# Sheet1.net
KiCad netlist of a schematic drawn in Altium Designer
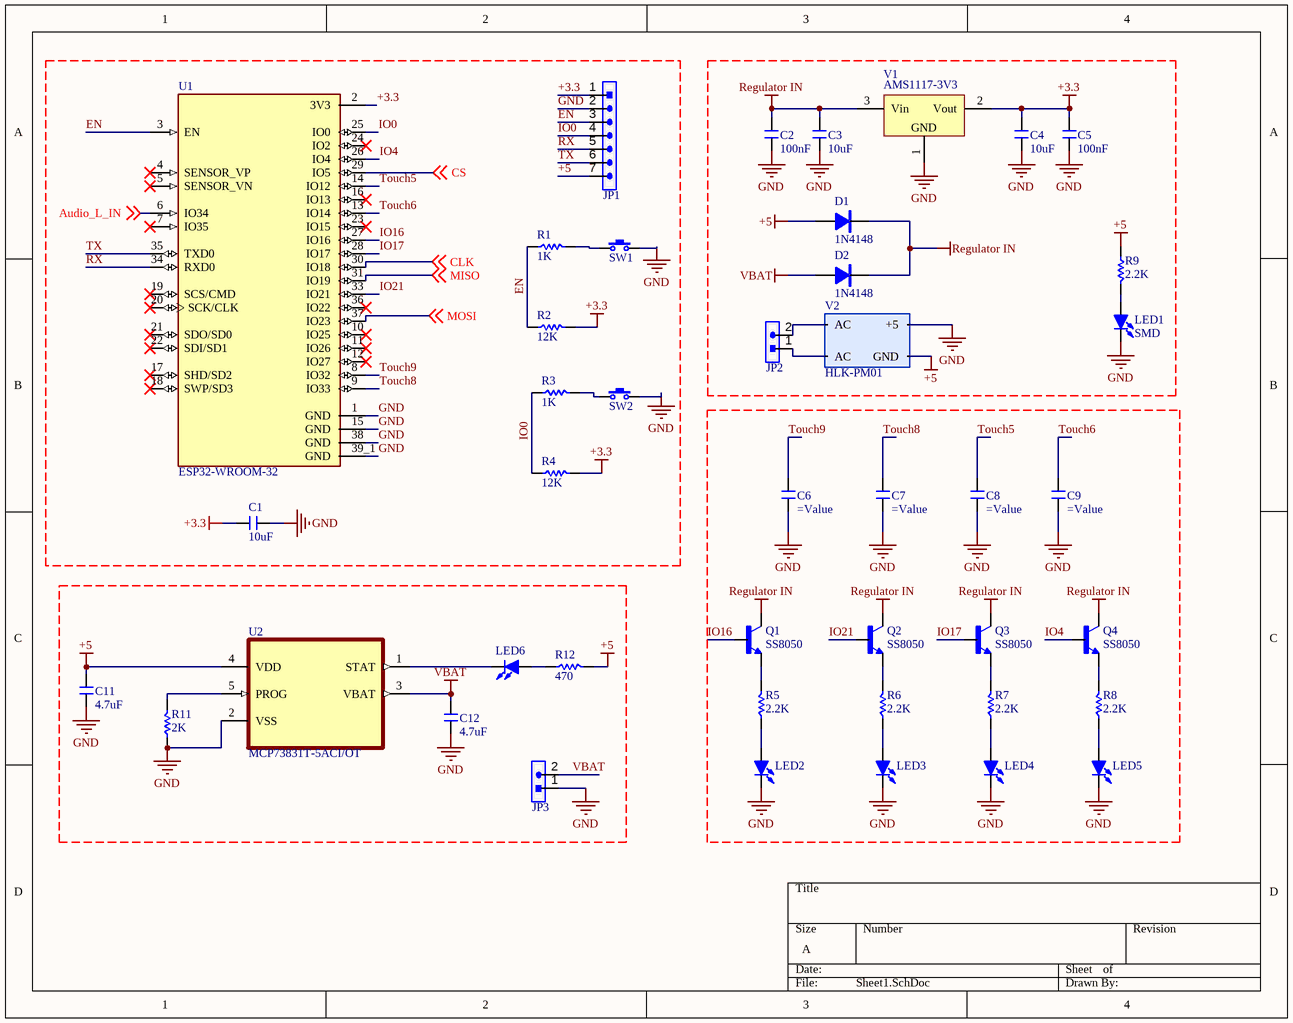
[diagram p0: Sheet1.SchDoc]

(export (version "E")
  (design (tool "Eeschema 10.0.6"))
  (components
    (comp (ref "C1")
      (value "10uF")
      (footprint "C 0805")
      (description "Non-polar patch capacitor")
      (fields (field (name "版权归属") "源创客"))
      (libsource (lib "Passive (Resistor-Capacitor-Inductor-Veristor-Ferrite)") (part "C"))
    )
    (comp (ref "C2")
      (value "100nF")
      (footprint "C 0805")
      (description "Non-polar patch capacitor")
      (fields (field (name "版权归属") "源创客"))
      (libsource (lib "Passive (Resistor-Capacitor-Inductor-Veristor-Ferrite)") (part "C"))
    )
    (comp (ref "C3")
      (value "10uF")
      (footprint "C 0805")
      (description "Non-polar patch capacitor")
      (fields (field (name "版权归属") "源创客"))
      (libsource (lib "Passive (Resistor-Capacitor-Inductor-Veristor-Ferrite)") (part "C"))
    )
    (comp (ref "C4")
      (value "10uF")
      (footprint "C 0805")
      (description "Non-polar patch capacitor")
      (fields (field (name "版权归属") "源创客"))
      (libsource (lib "Passive (Resistor-Capacitor-Inductor-Veristor-Ferrite)") (part "C"))
    )
    (comp (ref "C5")
      (value "100nF")
      (footprint "C 0805")
      (description "Non-polar patch capacitor")
      (fields (field (name "版权归属") "源创客"))
      (libsource (lib "Passive (Resistor-Capacitor-Inductor-Veristor-Ferrite)") (part "C"))
    )
    (comp (ref "C6")
      (value "~")
      (footprint "C 0805")
      (description "Non-polar patch capacitor")
      (fields (field (name "版权归属") "源创客"))
      (libsource (lib "Passive (Resistor-Capacitor-Inductor-Veristor-Ferrite)") (part "C"))
    )
    (comp (ref "C7")
      (value "~")
      (footprint "C 0805")
      (description "Non-polar patch capacitor")
      (fields (field (name "版权归属") "源创客"))
      (libsource (lib "Passive (Resistor-Capacitor-Inductor-Veristor-Ferrite)") (part "C"))
    )
    (comp (ref "C8")
      (value "~")
      (footprint "C 0805")
      (description "Non-polar patch capacitor")
      (fields (field (name "版权归属") "源创客"))
      (libsource (lib "Passive (Resistor-Capacitor-Inductor-Veristor-Ferrite)") (part "C"))
    )
    (comp (ref "C9")
      (value "~")
      (footprint "C 0805")
      (description "Non-polar patch capacitor")
      (fields (field (name "版权归属") "源创客"))
      (libsource (lib "Passive (Resistor-Capacitor-Inductor-Veristor-Ferrite)") (part "C"))
    )
    (comp (ref "C11")
      (value "4.7uF")
      (footprint "C 0805")
      (description "Non-polar patch capacitor")
      (fields (field (name "版权归属") "源创客"))
      (libsource (lib "Passive (Resistor-Capacitor-Inductor-Veristor-Ferrite)") (part "C"))
    )
    (comp (ref "C12")
      (value "4.7uF")
      (footprint "C 0805")
      (description "Non-polar patch capacitor")
      (fields (field (name "版权归属") "源创客"))
      (libsource (lib "Passive (Resistor-Capacitor-Inductor-Veristor-Ferrite)") (part "C"))
    )
    (comp (ref "D1")
      (value "1N4148")
      (footprint "MINI_MELF (LL34)")
      (description "High speed switching diode")
      (fields (field (name "版权归属") "源创客"))
      (libsource (lib "Diode-Zener-Rectifier Bridge") (part "1N4148"))
    )
    (comp (ref "D2")
      (value "1N4148")
      (footprint "MINI_MELF (LL34)")
      (description "High speed switching diode")
      (fields (field (name "版权归属") "源创客"))
      (libsource (lib "Diode-Zener-Rectifier Bridge") (part "1N4148"))
    )
    (comp (ref "JP1")
      (value "HDR-1X7")
      (footprint "HDR-1X7")
      (description "7P Connector")
      (fields (field (name "版权归属") "源创客"))
      (libsource (lib "Connectors") (part "Header 7"))
    )
    (comp (ref "JP2")
      (value "HDR-1X2")
      (footprint "KF2EDGK-2P")
      (description "2P Connector")
      (fields (field (name "版权归属") "源创客"))
      (libsource (lib "Connectors") (part "Header 2"))
    )
    (comp (ref "JP3")
      (value "HDR-1X2")
      (footprint "HDR-1X2")
      (description "2P Connector")
      (fields (field (name "版权归属") "源创客"))
      (libsource (lib "Connectors") (part "Header 2"))
    )
    (comp (ref "LED1")
      (value "SMD")
      (footprint "LED 0805R")
      (description "RED LED")
      (fields (field (name "版权归属") "源创客"))
      (libsource (lib "LED") (part "LED-SMD"))
    )
    (comp (ref "LED2")
      (value "~")
      (footprint "LED 5MM-B")
      (description "5mm plug-in LED")
      (fields (field (name "版权归属") "源创客"))
      (libsource (lib "LED") (part "LED-5MM"))
    )
    (comp (ref "LED3")
      (value "~")
      (footprint "LED 5MM-B")
      (description "5mm plug-in LED")
      (fields (field (name "版权归属") "源创客"))
      (libsource (lib "LED") (part "LED-5MM"))
    )
    (comp (ref "LED4")
      (value "~")
      (footprint "LED 5MM-B")
      (description "5mm plug-in LED")
      (fields (field (name "版权归属") "源创客"))
      (libsource (lib "LED") (part "LED-5MM"))
    )
    (comp (ref "LED5")
      (value "~")
      (footprint "LED 5MM-B")
      (description "5mm plug-in LED")
      (fields (field (name "版权归属") "源创客"))
      (libsource (lib "LED") (part "LED-5MM"))
    )
    (comp (ref "LED6")
      (value "LED-SMD")
      (footprint "LED 0805G")
      (description "Patch LED")
      (fields (field (name "版权归属") "源创客"))
      (libsource (lib "LED") (part "LED-SMD"))
    )
    (comp (ref "Q1")
      (value "SS8050")
      (footprint "SOT23-BEC")
      (description "Bipolar _BJT_ Transistor NPN General Purpose Amplifier Surface Mount")
      (fields (field (name "MF") "ON Semiconductor") (field (name "MP") "BCW31"))
      (libsource (lib "BCW31_") (part "BCW31*"))
    )
    (comp (ref "Q2")
      (value "SS8050")
      (footprint "SOT23-BEC")
      (description "Bipolar _BJT_ Transistor NPN General Purpose Amplifier Surface Mount")
      (fields (field (name "MF") "ON Semiconductor") (field (name "MP") "BCW31"))
      (libsource (lib "BCW31_") (part "BCW31*"))
    )
    (comp (ref "Q3")
      (value "SS8050")
      (footprint "SOT23-BEC")
      (description "Bipolar _BJT_ Transistor NPN General Purpose Amplifier Surface Mount")
      (fields (field (name "MF") "ON Semiconductor") (field (name "MP") "BCW31"))
      (libsource (lib "BCW31_") (part "BCW31*"))
    )
    (comp (ref "Q4")
      (value "SS8050")
      (footprint "SOT23-BEC")
      (description "Bipolar _BJT_ Transistor NPN General Purpose Amplifier Surface Mount")
      (fields (field (name "MF") "ON Semiconductor") (field (name "MP") "BCW31"))
      (libsource (lib "BCW31_") (part "BCW31*"))
    )
    (comp (ref "R1")
      (value "1K")
      (footprint "R 0805")
      (description "Chip resistor")
      (fields (field (name "版权归属") "源创客"))
      (libsource (lib "AltiumDesigner PCB Library") (part "R"))
    )
    (comp (ref "R2")
      (value "12K")
      (footprint "R 0805")
      (description "Chip resistor")
      (fields (field (name "版权归属") "源创客"))
      (libsource (lib "AltiumDesigner PCB Library") (part "R"))
    )
    (comp (ref "R3")
      (value "1K")
      (footprint "R 0805")
      (description "Chip resistor")
      (fields (field (name "版权归属") "源创客"))
      (libsource (lib "AltiumDesigner PCB Library") (part "R"))
    )
    (comp (ref "R4")
      (value "12K")
      (footprint "R 0805")
      (description "Chip resistor")
      (fields (field (name "版权归属") "源创客"))
      (libsource (lib "AltiumDesigner PCB Library") (part "R"))
    )
    (comp (ref "R5")
      (value "2.2K")
      (footprint "R 0805")
      (description "Chip resistor")
      (fields (field (name "版权归属") "源创客"))
      (libsource (lib "AltiumDesigner PCB Library") (part "R"))
    )
    (comp (ref "R6")
      (value "2.2K")
      (footprint "R 0805")
      (description "Chip resistor")
      (fields (field (name "版权归属") "源创客"))
      (libsource (lib "AltiumDesigner PCB Library") (part "R"))
    )
    (comp (ref "R7")
      (value "2.2K")
      (footprint "R 0805")
      (description "Chip resistor")
      (fields (field (name "版权归属") "源创客"))
      (libsource (lib "AltiumDesigner PCB Library") (part "R"))
    )
    (comp (ref "R8")
      (value "2.2K")
      (footprint "R 0805")
      (description "Chip resistor")
      (fields (field (name "版权归属") "源创客"))
      (libsource (lib "AltiumDesigner PCB Library") (part "R"))
    )
    (comp (ref "R9")
      (value "2.2K")
      (footprint "R 0805")
      (description "Chip resistor")
      (fields (field (name "版权归属") "源创客"))
      (libsource (lib "Passive (Resistor-Capacitor-Inductor-Veristor-Ferrite)") (part "R"))
    )
    (comp (ref "R11")
      (value "2K")
      (footprint "R 0805")
      (description "Chip resistor")
      (fields (field (name "版权归属") "源创客"))
      (libsource (lib "Passive (Resistor-Capacitor-Inductor-Veristor-Ferrite)") (part "R"))
    )
    (comp (ref "R12")
      (value "470")
      (footprint "R 0805")
      (description "Chip resistor")
      (fields (field (name "版权归属") "源创客"))
      (libsource (lib "Passive (Resistor-Capacitor-Inductor-Veristor-Ferrite)") (part "R"))
    )
    (comp (ref "SW1")
      (value "3x6x5")
      (footprint "TSW SMD-3*6*2.5")
      (description "3x6 tact switch")
      (fields (field (name "版权归属") "源创客"))
      (libsource (lib "Button") (part "TSW 3x6"))
    )
    (comp (ref "SW2")
      (value "3x6x5")
      (footprint "TSW SMD-3*6*2.5")
      (description "3x6 tact switch")
      (fields (field (name "版权归属") "源创客"))
      (libsource (lib "Button") (part "TSW 3x6"))
    )
    (comp (ref "U1")
      (value "ESP32-WROOM-32")
      (footprint "MODULE_ESP32-WROOM-32")
      (description "Bluetooth, WiFi Transceiver Module 2.4GHz ~ 2.5GHz Surface Mount")
      (fields (field (name "MF") "Espressif Systems") (field (name "DIGI-KEY_PART_NUMBER") "1904-1010-1-ND"))
      (libsource (lib "ESP32-WROOM-32") (part "ESP32-WROOM-32"))
    )
    (comp (ref "U2")
      (value "MCP73831T-5ACI/OT")
      (footprint "SOT95P280X145-5N")
      (description "Charger IC Lithium Ion/Polymer SOT-23-5")
      (fields (field (name "MF") "Microchip"))
      (libsource (lib "MCP73831T-5ACI_OT") (part "MCP73831T-5ACI/OT"))
    )
    (comp (ref "V1")
      (value "AMS1117-3V3")
      (footprint "SOT223_L")
      (description "Three-terminal regulator chip")
      (fields (field (name "版权归属") "源创客"))
      (libsource (lib "Integrated Circuit") (part "AMS1117"))
    )
    (comp (ref "V2")
      (value "HLK-PM01")
      (footprint "HLKPM01")
      (fields (field (name "MF") "Hi-link") (field (name "MP") "hlk-pm01"))
      (libsource (lib "HLK-PM01") (part "HLK-PM01"))
    )
  )
  (nets
    (net (code "1") (name "+3.3") (class "Default")
      (node (ref "C1") (pin "2") (pinfunction "2_2") (pintype "passive"))
      (node (ref "C4") (pin "2") (pinfunction "2_2") (pintype "passive"))
      (node (ref "C5") (pin "2") (pinfunction "2_2") (pintype "passive"))
      (node (ref "JP1") (pin "1") (pintype "passive"))
      (node (ref "R2") (pin "2") (pinfunction "2_2") (pintype "passive"))
      (node (ref "R4") (pin "2") (pinfunction "2_2") (pintype "passive"))
      (node (ref "U1") (pin "2") (pinfunction "3V3_2") (pintype "power_in"))
      (node (ref "V1") (pin "2") (pinfunction "Vout_2") (pintype "passive"))
    )
    (net (code "2") (name "+5") (class "Default")
      (node (ref "C11") (pin "2") (pinfunction "2_2") (pintype "passive"))
      (node (ref "D1") (pin "1") (pinfunction "A_1") (pintype "passive"))
      (node (ref "JP1") (pin "7") (pintype "passive"))
      (node (ref "R12") (pin "2") (pinfunction "2_2") (pintype "passive"))
      (node (ref "R9") (pin "1") (pinfunction "1_1") (pintype "passive"))
      (node (ref "U2") (pin "4") (pinfunction "VDD_4") (pintype "power_in"))
      (node (ref "V2") (pin "4") (pinfunction "GND_4") (pintype "output"))
    )
    (net (code "3") (name "/EN") (class "Default")
      (node (ref "JP1") (pin "3") (pintype "passive"))
      (node (ref "R1") (pin "1") (pinfunction "1_1") (pintype "passive"))
      (node (ref "R2") (pin "1") (pinfunction "1_1") (pintype "passive"))
      (node (ref "U1") (pin "3") (pinfunction "EN_3") (pintype "input"))
    )
    (net (code "4") (name "/IO0") (class "Default")
      (node (ref "JP1") (pin "4") (pintype "passive"))
      (node (ref "R3") (pin "1") (pinfunction "1_1") (pintype "passive"))
      (node (ref "R4") (pin "1") (pinfunction "1_1") (pintype "passive"))
      (node (ref "U1") (pin "25") (pinfunction "IO0_25") (pintype "bidirectional"))
    )
    (net (code "5") (name "/IO4") (class "Default")
      (node (ref "Q4") (pin "B") (pinfunction "B_B") (pintype "passive"))
      (node (ref "U1") (pin "26") (pinfunction "IO4_26") (pintype "bidirectional"))
    )
    (net (code "6") (name "/IO16") (class "Default")
      (node (ref "Q1") (pin "B") (pinfunction "B_B") (pintype "passive"))
      (node (ref "U1") (pin "27") (pinfunction "IO16_27") (pintype "bidirectional"))
    )
    (net (code "7") (name "/IO17") (class "Default")
      (node (ref "Q3") (pin "B") (pinfunction "B_B") (pintype "passive"))
      (node (ref "U1") (pin "28") (pinfunction "IO17_28") (pintype "bidirectional"))
    )
    (net (code "8") (name "/IO21") (class "Default")
      (node (ref "Q2") (pin "B") (pinfunction "B_B") (pintype "passive"))
      (node (ref "U1") (pin "33") (pinfunction "IO21_33") (pintype "bidirectional"))
    )
    (net (code "9") (name "/RX") (class "Default")
      (node (ref "JP1") (pin "5") (pintype "passive"))
      (node (ref "U1") (pin "34") (pinfunction "RXD0_34") (pintype "bidirectional"))
    )
    (net (code "10") (name "/TX") (class "Default")
      (node (ref "JP1") (pin "6") (pintype "passive"))
      (node (ref "U1") (pin "35") (pinfunction "TXD0_35") (pintype "bidirectional"))
    )
    (net (code "11") (name "/Touch5") (class "Default")
      (node (ref "C8") (pin "2") (pinfunction "2_2") (pintype "passive"))
      (node (ref "U1") (pin "14") (pinfunction "IO12_14") (pintype "bidirectional"))
    )
    (net (code "12") (name "/Touch6") (class "Default")
      (node (ref "C9") (pin "2") (pinfunction "2_2") (pintype "passive"))
      (node (ref "U1") (pin "13") (pinfunction "IO14_13") (pintype "bidirectional"))
    )
    (net (code "13") (name "/Touch8") (class "Default")
      (node (ref "C7") (pin "2") (pinfunction "2_2") (pintype "passive"))
      (node (ref "U1") (pin "9") (pinfunction "IO33_9") (pintype "bidirectional"))
    )
    (net (code "14") (name "/Touch9") (class "Default")
      (node (ref "C6") (pin "2") (pinfunction "2_2") (pintype "passive"))
      (node (ref "U1") (pin "8") (pinfunction "IO32_8") (pintype "bidirectional"))
    )
    (net (code "15") (name "Audio_L_IN") (class "Default")
      (node (ref "U1") (pin "6") (pinfunction "IO34_6") (pintype "input"))
    )
    (net (code "16") (name "CLK") (class "Default")
      (node (ref "U1") (pin "30") (pinfunction "IO18_30") (pintype "bidirectional"))
    )
    (net (code "17") (name "CS") (class "Default")
      (node (ref "U1") (pin "29") (pinfunction "IO5_29") (pintype "bidirectional"))
    )
    (net (code "18") (name "GND") (class "Default")
      (node (ref "C1") (pin "1") (pinfunction "1_1") (pintype "passive"))
      (node (ref "C11") (pin "1") (pinfunction "1_1") (pintype "passive"))
      (node (ref "C12") (pin "1") (pinfunction "1_1") (pintype "passive"))
      (node (ref "C2") (pin "1") (pinfunction "1_1") (pintype "passive"))
      (node (ref "C3") (pin "1") (pinfunction "1_1") (pintype "passive"))
      (node (ref "C4") (pin "1") (pinfunction "1_1") (pintype "passive"))
      (node (ref "C5") (pin "1") (pinfunction "1_1") (pintype "passive"))
      (node (ref "C6") (pin "1") (pinfunction "1_1") (pintype "passive"))
      (node (ref "C7") (pin "1") (pinfunction "1_1") (pintype "passive"))
      (node (ref "C8") (pin "1") (pinfunction "1_1") (pintype "passive"))
      (node (ref "C9") (pin "1") (pinfunction "1_1") (pintype "passive"))
      (node (ref "JP1") (pin "2") (pintype "passive"))
      (node (ref "JP3") (pin "1") (pintype "passive"))
      (node (ref "LED1") (pin "2") (pinfunction "K_2") (pintype "passive"))
      (node (ref "LED2") (pin "2") (pinfunction "K_2") (pintype "passive"))
      (node (ref "LED3") (pin "2") (pinfunction "K_2") (pintype "passive"))
      (node (ref "LED4") (pin "2") (pinfunction "K_2") (pintype "passive"))
      (node (ref "LED5") (pin "2") (pinfunction "K_2") (pintype "passive"))
      (node (ref "R11") (pin "1") (pinfunction "1_1") (pintype "passive"))
      (node (ref "SW1") (pin "2") (pinfunction "2_2") (pintype "passive"))
      (node (ref "SW2") (pin "2") (pinfunction "2_2") (pintype "passive"))
      (node (ref "U1") (pin "1") (pinfunction "GND_1") (pintype "power_in"))
      (node (ref "U1") (pin "15") (pinfunction "GND_15") (pintype "power_in"))
      (node (ref "U1") (pin "38") (pinfunction "GND_38") (pintype "power_in"))
      (node (ref "U1") (pin "39_1") (pinfunction "GND_39_1") (pintype "power_in"))
      (node (ref "U2") (pin "2") (pinfunction "VSS_2") (pintype "power_in"))
      (node (ref "V1") (pin "1") (pinfunction "GND_1") (pintype "passive"))
      (node (ref "V2") (pin "3") (pinfunction "+5_3") (pintype "output"))
    )
    (net (code "19") (name "MISO") (class "Default")
      (node (ref "U1") (pin "31") (pinfunction "IO19_31") (pintype "bidirectional"))
    )
    (net (code "20") (name "MOSI") (class "Default")
      (node (ref "U1") (pin "37") (pinfunction "IO23_37") (pintype "bidirectional"))
    )
    (net (code "21") (name "Net-(JP2-Pad1)") (class "Default")
      (node (ref "JP2") (pin "1") (pintype "passive"))
      (node (ref "V2") (pin "2") (pinfunction "AC_2") (pintype "input"))
    )
    (net (code "22") (name "Net-(JP2-Pad2)") (class "Default")
      (node (ref "JP2") (pin "2") (pintype "passive"))
      (node (ref "V2") (pin "1") (pinfunction "AC_1") (pintype "input"))
    )
    (net (code "23") (name "Net-(LED1-A)") (class "Default")
      (node (ref "LED1") (pin "1") (pinfunction "A_1") (pintype "passive"))
      (node (ref "R9") (pin "2") (pinfunction "2_2") (pintype "passive"))
    )
    (net (code "24") (name "Net-(LED2-A)") (class "Default")
      (node (ref "LED2") (pin "1") (pinfunction "A_1") (pintype "passive"))
      (node (ref "R5") (pin "1") (pinfunction "1_1") (pintype "passive"))
    )
    (net (code "25") (name "Net-(LED3-A)") (class "Default")
      (node (ref "LED3") (pin "1") (pinfunction "A_1") (pintype "passive"))
      (node (ref "R6") (pin "1") (pinfunction "1_1") (pintype "passive"))
    )
    (net (code "26") (name "Net-(LED4-A)") (class "Default")
      (node (ref "LED4") (pin "1") (pinfunction "A_1") (pintype "passive"))
      (node (ref "R7") (pin "1") (pinfunction "1_1") (pintype "passive"))
    )
    (net (code "27") (name "Net-(LED5-A)") (class "Default")
      (node (ref "LED5") (pin "1") (pinfunction "A_1") (pintype "passive"))
      (node (ref "R8") (pin "1") (pinfunction "1_1") (pintype "passive"))
    )
    (net (code "28") (name "Net-(LED6-A)") (class "Default")
      (node (ref "LED6") (pin "1") (pinfunction "A_1") (pintype "passive"))
      (node (ref "R12") (pin "1") (pinfunction "1_1") (pintype "passive"))
    )
    (net (code "29") (name "Net-(LED6-K)") (class "Default")
      (node (ref "LED6") (pin "2") (pinfunction "K_2") (pintype "passive"))
      (node (ref "U2") (pin "1") (pinfunction "STAT_1") (pintype "output"))
    )
    (net (code "30") (name "Net-(Q1-PadE)") (class "Default")
      (node (ref "Q1") (pin "E") (pinfunction "E_E") (pintype "passive"))
      (node (ref "R5") (pin "2") (pinfunction "2_2") (pintype "passive"))
    )
    (net (code "31") (name "Net-(Q2-PadE)") (class "Default")
      (node (ref "Q2") (pin "E") (pinfunction "E_E") (pintype "passive"))
      (node (ref "R6") (pin "2") (pinfunction "2_2") (pintype "passive"))
    )
    (net (code "32") (name "Net-(Q3-PadE)") (class "Default")
      (node (ref "Q3") (pin "E") (pinfunction "E_E") (pintype "passive"))
      (node (ref "R7") (pin "2") (pinfunction "2_2") (pintype "passive"))
    )
    (net (code "33") (name "Net-(Q4-PadE)") (class "Default")
      (node (ref "Q4") (pin "E") (pinfunction "E_E") (pintype "passive"))
      (node (ref "R8") (pin "2") (pinfunction "2_2") (pintype "passive"))
    )
    (net (code "34") (name "Net-(R1-Pad2)") (class "Default")
      (node (ref "R1") (pin "2") (pinfunction "2_2") (pintype "passive"))
      (node (ref "SW1") (pin "1") (pinfunction "1_1") (pintype "passive"))
    )
    (net (code "35") (name "Net-(R3-Pad2)") (class "Default")
      (node (ref "R3") (pin "2") (pinfunction "2_2") (pintype "passive"))
      (node (ref "SW2") (pin "1") (pinfunction "1_1") (pintype "passive"))
    )
    (net (code "36") (name "Net-(U2-PROG)") (class "Default")
      (node (ref "R11") (pin "2") (pinfunction "2_2") (pintype "passive"))
      (node (ref "U2") (pin "5") (pinfunction "PROG_5") (pintype "input"))
    )
    (net (code "37") (name "Regulator IN") (class "Default")
      (node (ref "C2") (pin "2") (pinfunction "2_2") (pintype "passive"))
      (node (ref "C3") (pin "2") (pinfunction "2_2") (pintype "passive"))
      (node (ref "D1") (pin "2") (pinfunction "K_2") (pintype "passive"))
      (node (ref "D2") (pin "2") (pinfunction "K_2") (pintype "passive"))
      (node (ref "Q1") (pin "C") (pinfunction "C_C") (pintype "passive"))
      (node (ref "Q2") (pin "C") (pinfunction "C_C") (pintype "passive"))
      (node (ref "Q3") (pin "C") (pinfunction "C_C") (pintype "passive"))
      (node (ref "Q4") (pin "C") (pinfunction "C_C") (pintype "passive"))
      (node (ref "V1") (pin "3") (pinfunction "Vin_3") (pintype "passive"))
    )
    (net (code "38") (name "VBAT") (class "Default")
      (node (ref "C12") (pin "2") (pinfunction "2_2") (pintype "passive"))
      (node (ref "D2") (pin "1") (pinfunction "A_1") (pintype "passive"))
      (node (ref "JP3") (pin "2") (pintype "passive"))
      (node (ref "U2") (pin "3") (pinfunction "VBAT_3") (pintype "output"))
    )
    (net (code "39") (name "unconnected-(U1-IO2-Pad24)") (class "Default")
      (node (ref "U1") (pin "24") (pinfunction "IO2_24") (pintype "bidirectional+no_connect"))
    )
    (net (code "40") (name "unconnected-(U1-IO13-Pad16)") (class "Default")
      (node (ref "U1") (pin "16") (pinfunction "IO13_16") (pintype "bidirectional+no_connect"))
    )
    (net (code "41") (name "unconnected-(U1-IO15-Pad23)") (class "Default")
      (node (ref "U1") (pin "23") (pinfunction "IO15_23") (pintype "bidirectional+no_connect"))
    )
    (net (code "42") (name "unconnected-(U1-IO22-Pad36)") (class "Default")
      (node (ref "U1") (pin "36") (pinfunction "IO22_36") (pintype "bidirectional+no_connect"))
    )
    (net (code "43") (name "unconnected-(U1-IO25-Pad10)") (class "Default")
      (node (ref "U1") (pin "10") (pinfunction "IO25_10") (pintype "bidirectional+no_connect"))
    )
    (net (code "44") (name "unconnected-(U1-IO26-Pad11)") (class "Default")
      (node (ref "U1") (pin "11") (pinfunction "IO26_11") (pintype "bidirectional+no_connect"))
    )
    (net (code "45") (name "unconnected-(U1-IO27-Pad12)") (class "Default")
      (node (ref "U1") (pin "12") (pinfunction "IO27_12") (pintype "bidirectional+no_connect"))
    )
    (net (code "46") (name "unconnected-(U1-IO35-Pad7)") (class "Default")
      (node (ref "U1") (pin "7") (pinfunction "IO35_7") (pintype "input+no_connect"))
    )
    (net (code "47") (name "unconnected-(U1-SCK{slash}CLK-Pad20)") (class "Default")
      (node (ref "U1") (pin "20") (pinfunction "SCK/CLK_20") (pintype "bidirectional+no_connect"))
    )
    (net (code "48") (name "unconnected-(U1-SCS{slash}CMD-Pad19)") (class "Default")
      (node (ref "U1") (pin "19") (pinfunction "SCS/CMD_19") (pintype "bidirectional+no_connect"))
    )
    (net (code "49") (name "unconnected-(U1-SDI{slash}SD1-Pad22)") (class "Default")
      (node (ref "U1") (pin "22") (pinfunction "SDI/SD1_22") (pintype "bidirectional+no_connect"))
    )
    (net (code "50") (name "unconnected-(U1-SDO{slash}SD0-Pad21)") (class "Default")
      (node (ref "U1") (pin "21") (pinfunction "SDO/SD0_21") (pintype "bidirectional+no_connect"))
    )
    (net (code "51") (name "unconnected-(U1-SENSOR_VN-Pad5)") (class "Default")
      (node (ref "U1") (pin "5") (pinfunction "SENSOR_VN_5") (pintype "input+no_connect"))
    )
    (net (code "52") (name "unconnected-(U1-SENSOR_VP-Pad4)") (class "Default")
      (node (ref "U1") (pin "4") (pinfunction "SENSOR_VP_4") (pintype "input+no_connect"))
    )
    (net (code "53") (name "unconnected-(U1-SHD{slash}SD2-Pad17)") (class "Default")
      (node (ref "U1") (pin "17") (pinfunction "SHD/SD2_17") (pintype "bidirectional+no_connect"))
    )
    (net (code "54") (name "unconnected-(U1-SWP{slash}SD3-Pad18)") (class "Default")
      (node (ref "U1") (pin "18") (pinfunction "SWP/SD3_18") (pintype "bidirectional+no_connect"))
    )
  )
)
